# LightStateRF.net
KiCad netlist of a schematic drawn in Altium Designer
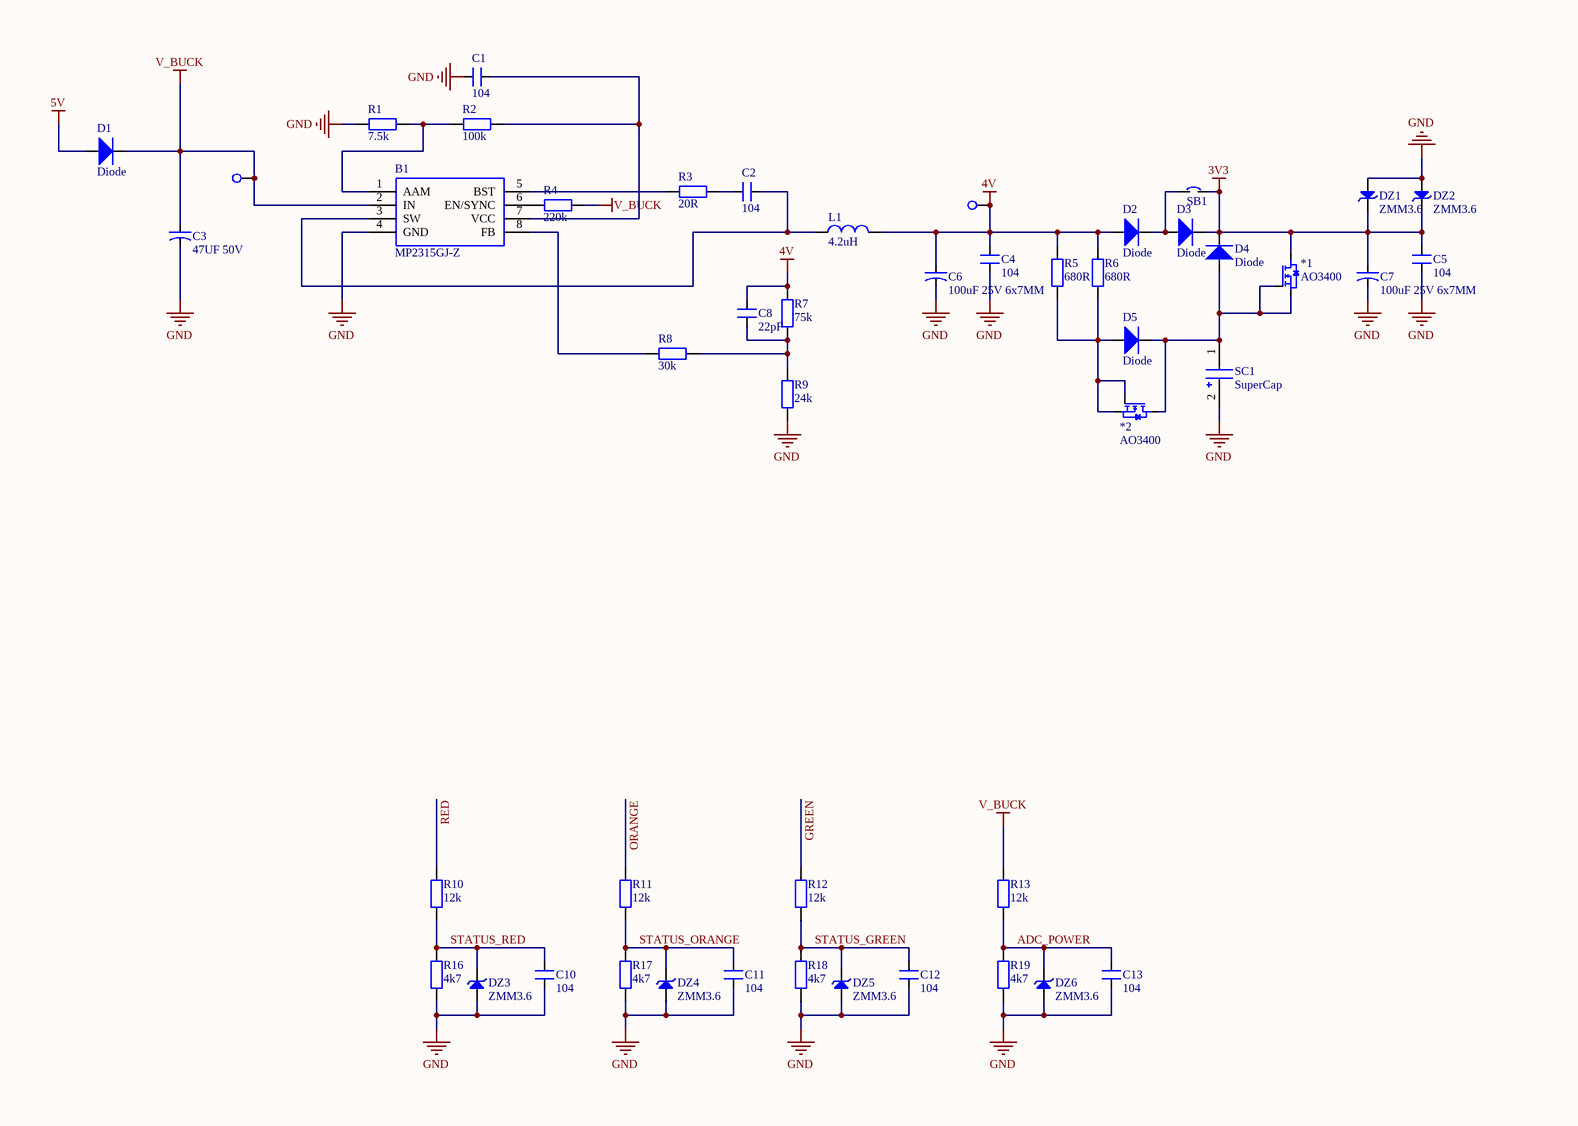
[diagram p0: LightStateRF.SchDoc, top left]
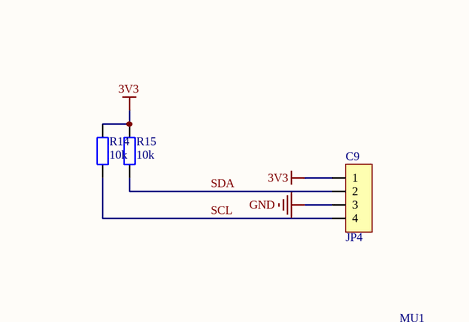
[diagram p1: LightStateRF.SchDoc, top right]
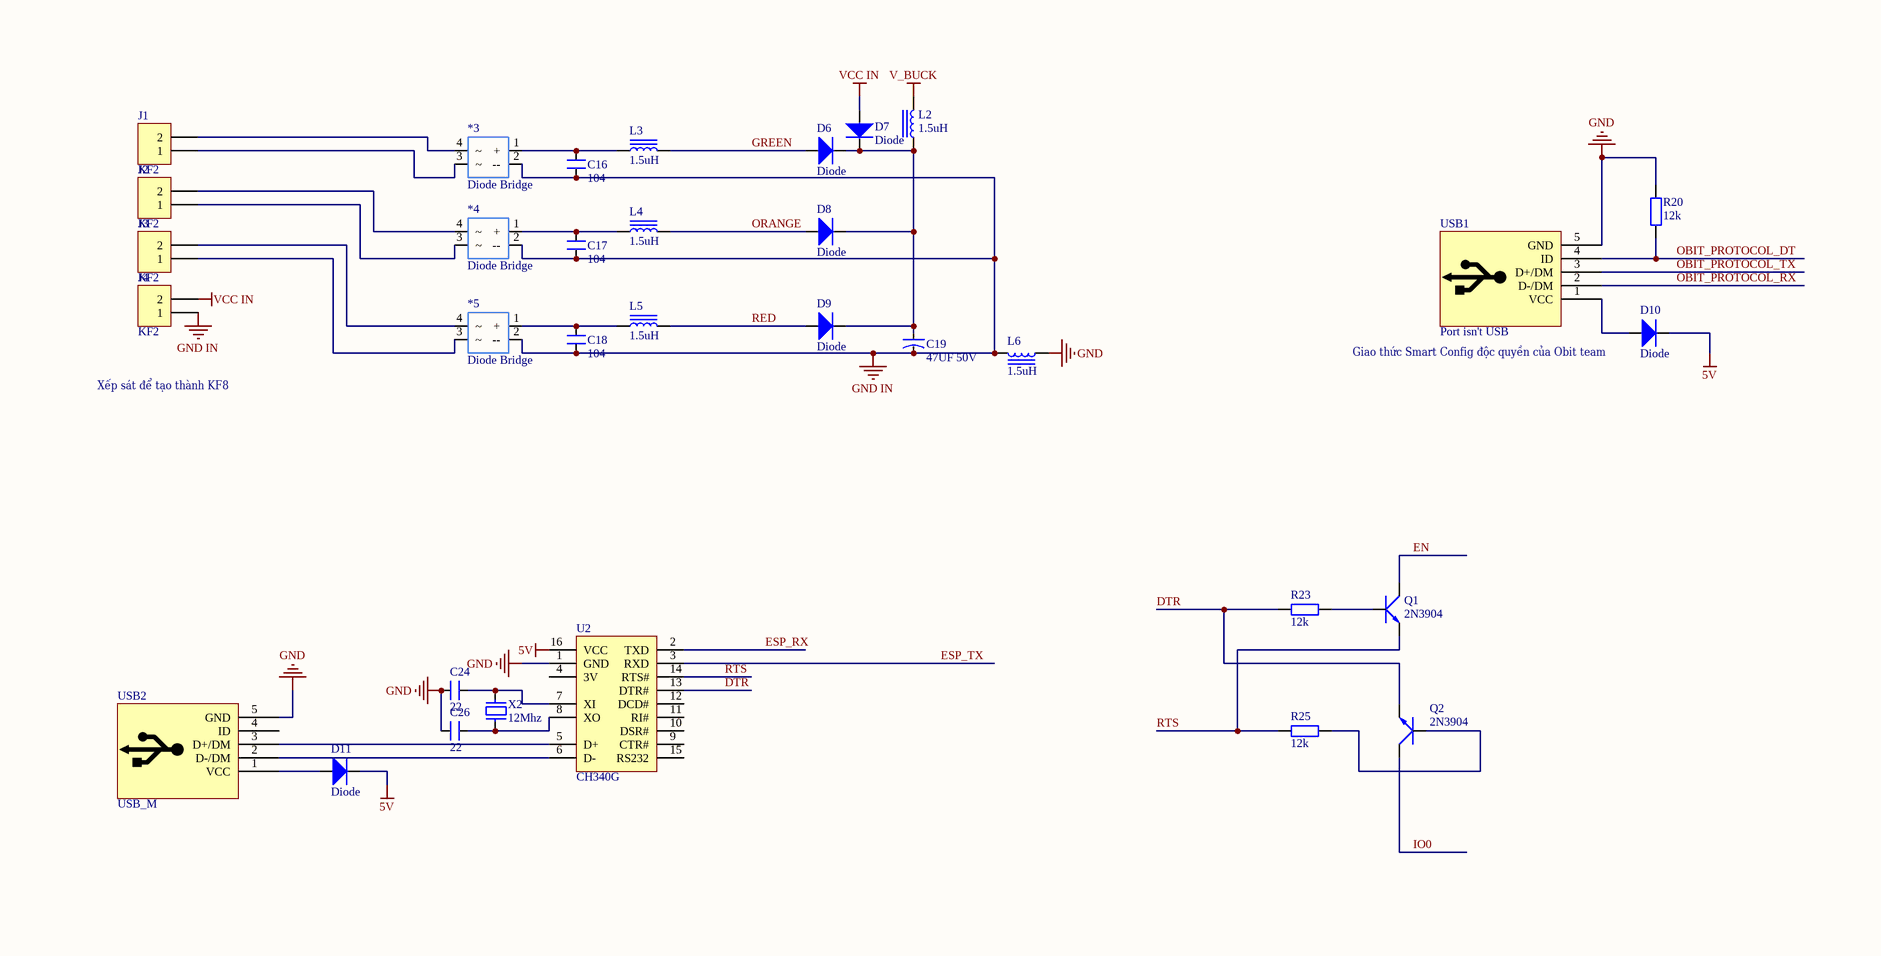
[diagram p2: LightStateRF.SchDoc, bottom left]
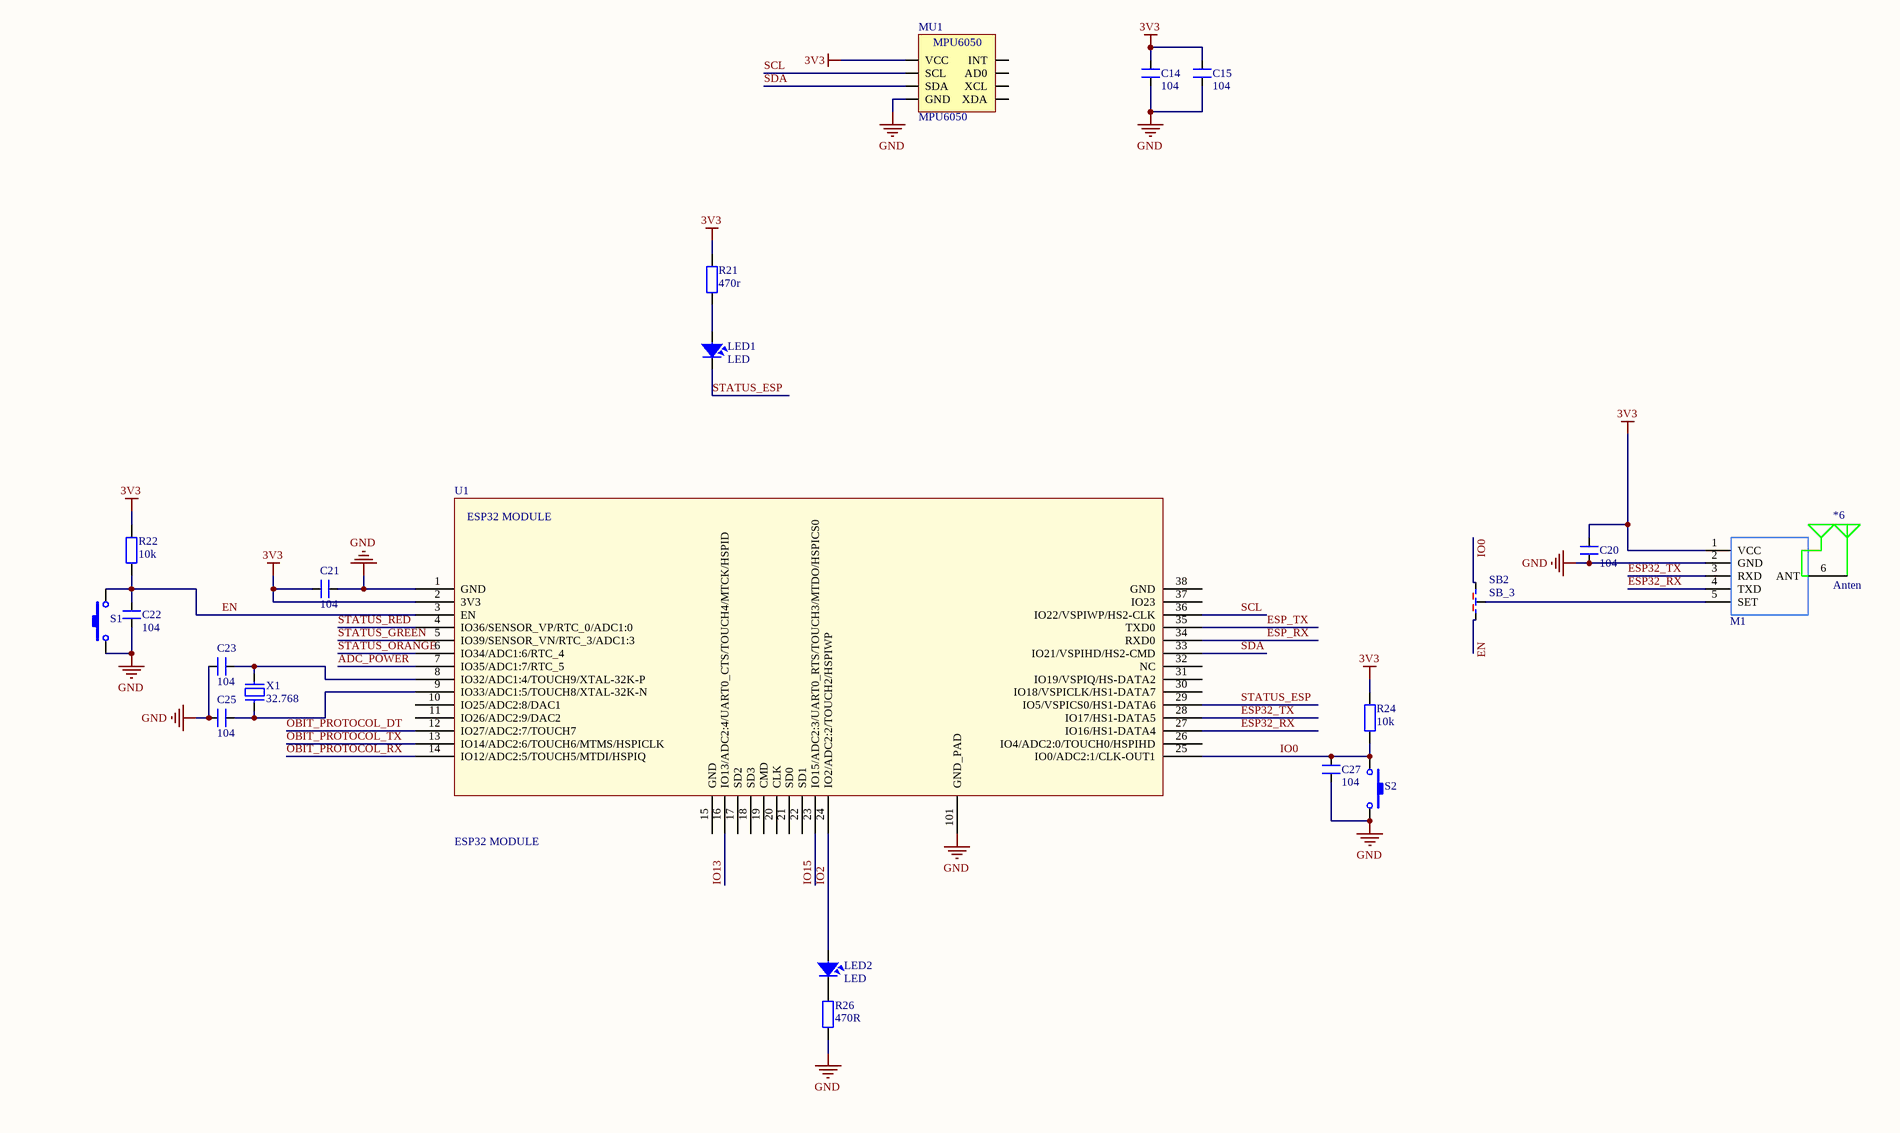
[diagram p3: LightStateRF.SchDoc, bottom right]

(export (version "E")
  (design (tool "Eeschema 10.0.6"))
  (components
    (comp (ref "*1") (value "AO3400") (footprint "SOT23-123") (libsource (lib "OBIT_TESLA") (part "AO3400")))
    (comp (ref "*2") (value "AO3400") (footprint "SOT23-123") (libsource (lib "OBIT_TESLA") (part "AO3400")))
    (comp (ref "*3")
      (value "Diode Bridge")
      (footprint "Diode Bridge 1A")
      (libsource (lib "OBIT_TESLA") (part "Diode Bridge"))
    )
    (comp (ref "*4")
      (value "Diode Bridge")
      (footprint "Diode Bridge 1A")
      (libsource (lib "OBIT_TESLA") (part "Diode Bridge"))
    )
    (comp (ref "*5")
      (value "Diode Bridge")
      (footprint "Diode Bridge 1A")
      (libsource (lib "OBIT_TESLA") (part "Diode Bridge"))
    )
    (comp (ref "*6")
      (value "Anten")
      (footprint "LOXO_433_NGANG")
      (libsource (lib "OBIT_TESLA") (part "Anten"))
    )
    (comp (ref "*TP1") (value "TP") (footprint "TP") (libsource (lib "OBIT_TESLA") (part "TP")))
    (comp (ref "*TP2") (value "TP") (footprint "TP") (libsource (lib "OBIT_TESLA") (part "TP")))
    (comp (ref "B1")
      (value "MP2315GJ-Z")
      (footprint "SOT65P280X100-8N")
      (description "Switching Voltage Regulators 3A 24V 500kHz Sync buck")
      (libsource (lib "OBIT_TESLA") (part "MP2315GJ-Z"))
    )
    (comp (ref "C1")
      (value "104")
      (footprint "SM-0805")
      (description "Cap SMD")
      (libsource (lib "OBIT_TESLA") (part "CM"))
    )
    (comp (ref "C2")
      (value "104")
      (footprint "SM-0805")
      (description "Cap SMD")
      (libsource (lib "OBIT_TESLA") (part "CM"))
    )
    (comp (ref "C3")
      (value "47UF 50V")
      (footprint "CAP-ALU-SMD-6.3x7.7x2.2")
      (description "Tụ Nhôm 47UF 50V 6.3x5.5MM")
      (fields (field (name "PUBLISHER") "Altium Limited"))
      (libsource (lib "Tesla_Thinh") (part "CN-ALU-SMD"))
    )
    (comp (ref "C4")
      (value "104")
      (footprint "SM-0805")
      (description "Cap SMD")
      (libsource (lib "OBIT_TESLA") (part "CM"))
    )
    (comp (ref "C5")
      (value "104")
      (footprint "SM-0805")
      (description "Cap SMD")
      (libsource (lib "OBIT_TESLA") (part "CM"))
    )
    (comp (ref "C6")
      (value "100uF 25V 6x7MM")
      (footprint "CAP-ALU-SMD-6.3x7.7x2.2")
      (description "Polarized Capacitor (Axial)")
      (fields (field (name "PUBLISHER") "Altium Limited"))
      (libsource (lib "Tesla_Thinh") (part "CN-ALU-SMD"))
    )
    (comp (ref "C7")
      (value "100uF 25V 6x7MM")
      (footprint "CAP-ALU-SMD-6.3x7.7x2.2")
      (description "Polarized Capacitor (Axial)")
      (fields (field (name "PUBLISHER") "Altium Limited"))
      (libsource (lib "Tesla_Thinh") (part "CN-ALU-SMD"))
    )
    (comp (ref "C8")
      (value "22pF")
      (footprint "SM-0805")
      (description "Cap SMD")
      (libsource (lib "OBIT_TESLA") (part "CM"))
    )
    (comp (ref "C9")
      (value "JP4")
      (footprint "JP4-C1T")
      (description "WR-PHD 2.54 mm Angled Socket Header")
      (fields
        (field (name "MANUFACTURER") "Würth Elektronik eiSos GmbH")
        (field (name "PARTNO") "613004143121")
        (field (name "CREATED BY") "Karrer Zheng")
      )
      (libsource (lib "OBIT_TESLA") (part "JP4"))
    )
    (comp (ref "C10")
      (value "104")
      (footprint "SM-0805")
      (description "Cap SMD")
      (libsource (lib "OBIT_TESLA") (part "CM"))
    )
    (comp (ref "C11")
      (value "104")
      (footprint "SM-0805")
      (description "Cap SMD")
      (libsource (lib "OBIT_TESLA") (part "CM"))
    )
    (comp (ref "C12")
      (value "104")
      (footprint "SM-0805")
      (description "Cap SMD")
      (libsource (lib "OBIT_TESLA") (part "CM"))
    )
    (comp (ref "C13")
      (value "104")
      (footprint "SM-0805")
      (description "Cap SMD")
      (libsource (lib "OBIT_TESLA") (part "CM"))
    )
    (comp (ref "C14")
      (value "104")
      (footprint "SM-0805")
      (description "Cap SMD")
      (libsource (lib "OBIT_TESLA") (part "CM"))
    )
    (comp (ref "C15")
      (value "104")
      (footprint "SM-0805")
      (description "Cap SMD")
      (libsource (lib "OBIT_TESLA") (part "CM"))
    )
    (comp (ref "C16")
      (value "104")
      (footprint "SM-0805")
      (description "Cap SMD")
      (libsource (lib "OBIT_TESLA") (part "CM"))
    )
    (comp (ref "C17")
      (value "104")
      (footprint "SM-0805")
      (description "Cap SMD")
      (libsource (lib "OBIT_TESLA") (part "CM"))
    )
    (comp (ref "C18")
      (value "104")
      (footprint "SM-0805")
      (description "Cap SMD")
      (libsource (lib "OBIT_TESLA") (part "CM"))
    )
    (comp (ref "C19")
      (value "47UF 50V")
      (footprint "CAP-ALU-SMD-6.3x7.7x2.2")
      (description "Tụ Nhôm 47UF 50V 6.3x5.5MM")
      (fields (field (name "PUBLISHER") "Altium Limited"))
      (libsource (lib "Tesla_Thinh") (part "CN-ALU-SMD"))
    )
    (comp (ref "C20")
      (value "104")
      (footprint "SM-0805")
      (description "Cap SMD")
      (libsource (lib "OBIT_TESLA") (part "CM"))
    )
    (comp (ref "C21")
      (value "104")
      (footprint "SM-0805")
      (description "Cap SMD")
      (libsource (lib "OBIT_TESLA") (part "CM"))
    )
    (comp (ref "C22")
      (value "104")
      (footprint "SM-0805")
      (description "Cap SMD")
      (libsource (lib "OBIT_TESLA") (part "CM"))
    )
    (comp (ref "C23")
      (value "104")
      (footprint "SM-0805")
      (description "Cap SMD")
      (libsource (lib "OBIT_TESLA") (part "CM"))
    )
    (comp (ref "C24")
      (value "22")
      (footprint "SM-0805")
      (description "Cap SMD")
      (libsource (lib "OBIT_TESLA") (part "CM"))
    )
    (comp (ref "C25")
      (value "104")
      (footprint "SM-0805")
      (description "Cap SMD")
      (libsource (lib "OBIT_TESLA") (part "CM"))
    )
    (comp (ref "C26")
      (value "22")
      (footprint "SM-0805")
      (description "Cap SMD")
      (libsource (lib "OBIT_TESLA") (part "CM"))
    )
    (comp (ref "C27")
      (value "104")
      (footprint "SM-0805")
      (description "Cap SMD")
      (libsource (lib "OBIT_TESLA") (part "CM"))
    )
    (comp (ref "D1") (value "Diode") (footprint "SOD123") (libsource (lib "OBIT_TESLA") (part "Diode")))
    (comp (ref "D2") (value "Diode") (footprint "DIO-SMD-123") (libsource (lib "OBIT_TESLA") (part "Diode")))
    (comp (ref "D3") (value "Diode") (footprint "DIO-SMD-123") (libsource (lib "OBIT_TESLA") (part "Diode")))
    (comp (ref "D4") (value "Diode") (footprint "DIO-SMD-123") (libsource (lib "OBIT_TESLA") (part "Diode")))
    (comp (ref "D5") (value "Diode") (footprint "SOD123") (libsource (lib "OBIT_TESLA") (part "Diode")))
    (comp (ref "D6") (value "Diode") (footprint "DIO-SMD-106") (libsource (lib "OBIT_TESLA") (part "Diode")))
    (comp (ref "D7") (value "Diode") (footprint "DIO-SMD-106") (libsource (lib "OBIT_TESLA") (part "Diode")))
    (comp (ref "D8") (value "Diode") (footprint "DIO-SMD-106") (libsource (lib "OBIT_TESLA") (part "Diode")))
    (comp (ref "D9") (value "Diode") (footprint "DIO-SMD-106") (libsource (lib "OBIT_TESLA") (part "Diode")))
    (comp (ref "D10") (value "Diode") (footprint "DIO-SMD-106") (libsource (lib "OBIT_TESLA") (part "Diode")))
    (comp (ref "D11") (value "Diode") (footprint "DIO-SMD-106") (libsource (lib "OBIT_TESLA") (part "Diode")))
    (comp (ref "DZ1")
      (value "ZMM3.6")
      (footprint "SOD123")
      (description "DIODE GEN PURP 75V 200MA LLDS")
      (libsource (lib "Library") (part "DIODE Zener"))
    )
    (comp (ref "DZ2")
      (value "ZMM3.6")
      (footprint "DIO-SMD-123")
      (description "DIODE GEN PURP 75V 200MA LLDS")
      (libsource (lib "Library") (part "DIODE Zener"))
    )
    (comp (ref "DZ3")
      (value "ZMM3.6")
      (footprint "SOD123")
      (description "DIODE GEN PURP 75V 200MA LLDS")
      (libsource (lib "Library") (part "DIODE Zener"))
    )
    (comp (ref "DZ4")
      (value "ZMM3.6")
      (footprint "SOD123")
      (description "DIODE GEN PURP 75V 200MA LLDS")
      (libsource (lib "Library") (part "DIODE Zener"))
    )
    (comp (ref "DZ5")
      (value "ZMM3.6")
      (footprint "SOD123")
      (description "DIODE GEN PURP 75V 200MA LLDS")
      (libsource (lib "Library") (part "DIODE Zener"))
    )
    (comp (ref "DZ6")
      (value "ZMM3.6")
      (footprint "SOD123")
      (description "DIODE GEN PURP 75V 200MA LLDS")
      (libsource (lib "Library") (part "DIODE Zener"))
    )
    (comp (ref "J1")
      (value "KF2")
      (footprint "KF2-5.08")
      (fields
        (field (name "MANUFACTURER") "Würth Elektronik eiSos GmbH")
        (field (name "PARTNO") "691103110002")
        (field (name "CREATED BY") "Karrer Zheng")
      )
      (libsource (lib "Tesla_Thinh") (part "KF2"))
    )
    (comp (ref "J2")
      (value "KF2")
      (footprint "KF2-5.08")
      (fields
        (field (name "MANUFACTURER") "Würth Elektronik eiSos GmbH")
        (field (name "PARTNO") "691103110002")
        (field (name "CREATED BY") "Karrer Zheng")
      )
      (libsource (lib "Tesla_Thinh") (part "KF2"))
    )
    (comp (ref "J3")
      (value "KF2")
      (footprint "KF2-5.08")
      (fields
        (field (name "MANUFACTURER") "Würth Elektronik eiSos GmbH")
        (field (name "PARTNO") "691103110002")
        (field (name "CREATED BY") "Karrer Zheng")
      )
      (libsource (lib "Tesla_Thinh") (part "KF2"))
    )
    (comp (ref "J4")
      (value "KF2")
      (footprint "KF2-5.08")
      (fields
        (field (name "MANUFACTURER") "Würth Elektronik eiSos GmbH")
        (field (name "PARTNO") "691103110002")
        (field (name "CREATED BY") "Karrer Zheng")
      )
      (libsource (lib "Tesla_Thinh") (part "KF2"))
    )
    (comp (ref "L1")
      (value "4.2uH")
      (footprint "IND 4532-2P")
      (libsource (lib "AltiumLibraryTieuBao (1)") (part "INDUCTOR B"))
    )
    (comp (ref "L2")
      (value "1.5uH")
      (footprint "FER 0805/2012")
      (description "SMT Inductor")
      (libsource (lib "OBIT_TESLA") (part "Inductor"))
    )
    (comp (ref "L3")
      (value "1.5uH")
      (footprint "FER 0805/2012")
      (description "SMT Inductor")
      (libsource (lib "OBIT_TESLA") (part "Inductor"))
    )
    (comp (ref "L4")
      (value "1.5uH")
      (footprint "FER 0805/2012")
      (description "SMT Inductor")
      (libsource (lib "OBIT_TESLA") (part "Inductor"))
    )
    (comp (ref "L5")
      (value "1.5uH")
      (footprint "FER 0805/2012")
      (description "SMT Inductor")
      (libsource (lib "OBIT_TESLA") (part "Inductor"))
    )
    (comp (ref "L6")
      (value "1.5uH")
      (footprint "FER 0805/2012")
      (description "SMT Inductor")
      (libsource (lib "OBIT_TESLA") (part "Inductor"))
    )
    (comp (ref "LED1")
      (value "LED")
      (footprint "SM-LED-0805-Blue")
      (libsource (lib "OBIT_TESLA") (part "LED"))
    )
    (comp (ref "LED2")
      (value "LED")
      (footprint "SM-LED-0805-Blue")
      (libsource (lib "OBIT_TESLA") (part "LED"))
    )
    (comp (ref "M1")
      (value "CC1101")
      (footprint "CC1101 UART HC11")
      (description "OBIT TEAM\r\nCC1101 UART 433MHZ")
      (libsource (lib "OBIT_TESLA") (part "CC1101 UART HC11"))
    )
    (comp (ref "MU1")
      (value "MPU6050")
      (footprint "MPU6050")
      (fields
        (field (name "MANUFACTURER") "Würth Elektronik eiSos GmbH")
        (field (name "PARTNO") "613004143121")
        (field (name "CREATED BY") "Karrer Zheng")
      )
      (libsource (lib "Tesla_Thinh") (part "MPU6050"))
    )
    (comp (ref "Q1")
      (value "2N3904")
      (footprint "SOT23-231")
      (description "NPN 600mW, ECB")
      (libsource (lib "OBIT_TESLA") (part "2N3904"))
    )
    (comp (ref "Q2")
      (value "2N3904")
      (footprint "SOT23-231")
      (description "NPN 600mW, ECB")
      (libsource (lib "OBIT_TESLA") (part "2N3904"))
    )
    (comp (ref "R1")
      (value "7.5k")
      (footprint "RES-SMD-0805")
      (description "Resistor R1/4W")
      (libsource (lib "OBIT_TESLA") (part "R"))
    )
    (comp (ref "R2")
      (value "100k")
      (footprint "RES-SMD-0805")
      (description "Resistor R1/4W")
      (libsource (lib "OBIT_TESLA") (part "R"))
    )
    (comp (ref "R3")
      (value "20R")
      (footprint "RES-SMD-0805")
      (description "Resistor R1/4W")
      (libsource (lib "OBIT_TESLA") (part "R"))
    )
    (comp (ref "R4")
      (value "220k")
      (footprint "RES-SMD-0805")
      (description "Resistor R1/4W")
      (libsource (lib "OBIT_TESLA") (part "R"))
    )
    (comp (ref "R5")
      (value "680R")
      (footprint "RES-SMD-0805")
      (description "Resistor R1/4W")
      (libsource (lib "OBIT_TESLA") (part "R"))
    )
    (comp (ref "R6")
      (value "680R")
      (footprint "RES-SMD-0805")
      (description "Resistor R1/4W")
      (libsource (lib "OBIT_TESLA") (part "R"))
    )
    (comp (ref "R7")
      (value "75k")
      (footprint "RES-SMD-0805")
      (description "Resistor R1/4W")
      (libsource (lib "OBIT_TESLA") (part "R"))
    )
    (comp (ref "R8")
      (value "30k")
      (footprint "RES-SMD-0805")
      (description "Resistor R1/4W")
      (libsource (lib "OBIT_TESLA") (part "R"))
    )
    (comp (ref "R9")
      (value "24k")
      (footprint "RES-SMD-0805")
      (description "Resistor R1/4W")
      (libsource (lib "OBIT_TESLA") (part "R"))
    )
    (comp (ref "R10")
      (value "12k")
      (footprint "RES-SMD-0805")
      (description "Resistor R1/4W")
      (libsource (lib "OBIT_TESLA") (part "R"))
    )
    (comp (ref "R11")
      (value "12k")
      (footprint "RES-SMD-0805")
      (description "Resistor R1/4W")
      (libsource (lib "OBIT_TESLA") (part "R"))
    )
    (comp (ref "R12")
      (value "12k")
      (footprint "RES-SMD-0805")
      (description "Resistor R1/4W")
      (libsource (lib "OBIT_TESLA") (part "R"))
    )
    (comp (ref "R13")
      (value "12k")
      (footprint "RES-SMD-0805")
      (description "Resistor R1/4W")
      (libsource (lib "OBIT_TESLA") (part "R"))
    )
    (comp (ref "R14")
      (value "10k")
      (footprint "RES-SMD-0805")
      (description "Resistor R1/4W")
      (libsource (lib "OBIT_TESLA") (part "R"))
    )
    (comp (ref "R15")
      (value "10k")
      (footprint "RES-SMD-0805")
      (description "Resistor R1/4W")
      (libsource (lib "OBIT_TESLA") (part "R"))
    )
    (comp (ref "R16")
      (value "4k7")
      (footprint "RES-SMD-0805")
      (description "Resistor R1/4W")
      (libsource (lib "OBIT_TESLA") (part "R"))
    )
    (comp (ref "R17")
      (value "4k7")
      (footprint "RES-SMD-0805")
      (description "Resistor R1/4W")
      (libsource (lib "OBIT_TESLA") (part "R"))
    )
    (comp (ref "R18")
      (value "4k7")
      (footprint "RES-SMD-0805")
      (description "Resistor R1/4W")
      (libsource (lib "OBIT_TESLA") (part "R"))
    )
    (comp (ref "R19")
      (value "4k7")
      (footprint "RES-SMD-0805")
      (description "Resistor R1/4W")
      (libsource (lib "OBIT_TESLA") (part "R"))
    )
    (comp (ref "R20")
      (value "12k")
      (footprint "RES-SMD-0805")
      (description "Resistor R1/4W")
      (libsource (lib "OBIT_TESLA") (part "R"))
    )
    (comp (ref "R21")
      (value "470r")
      (footprint "RES-SMD-0805")
      (description "Resistor R1/4W")
      (libsource (lib "OBIT_TESLA") (part "R"))
    )
    (comp (ref "R22")
      (value "10k")
      (footprint "RES-SMD-0805")
      (description "Resistor R1/4W")
      (libsource (lib "OBIT_TESLA") (part "R"))
    )
    (comp (ref "R23")
      (value "12k")
      (footprint "RES-SMD-0805")
      (description "Resistor R1/4W")
      (libsource (lib "OBIT_TESLA") (part "R"))
    )
    (comp (ref "R24")
      (value "10k")
      (footprint "RES-SMD-0805")
      (description "Resistor R1/4W")
      (libsource (lib "OBIT_TESLA") (part "R"))
    )
    (comp (ref "R25")
      (value "12k")
      (footprint "RES-SMD-0805")
      (description "Resistor R1/4W")
      (libsource (lib "OBIT_TESLA") (part "R"))
    )
    (comp (ref "R26")
      (value "470R")
      (footprint "RES-SMD-0805")
      (description "Resistor R1/4W")
      (libsource (lib "OBIT_TESLA") (part "R"))
    )
    (comp (ref "S1")
      (value "SW")
      (footprint "BUTTON-SMD 2PIN")
      (description "Switch-Button")
      (fields (field (name "PUBLISHER") "Altium Limited"))
      (libsource (lib "OBIT_TESLA") (part "SW-Button"))
    )
    (comp (ref "S2")
      (value "SW")
      (footprint "BUTTON-SMD 2PIN")
      (description "Switch-Button")
      (fields (field (name "PUBLISHER") "Altium Limited"))
      (libsource (lib "OBIT_TESLA") (part "SW-Button"))
    )
    (comp (ref "SB1") (value "SB") (footprint "SB") (libsource (lib "OBIT_TESLA") (part "SB")))
    (comp (ref "SB2") (value "SB_3") (footprint "SB_3") (libsource (lib "OBIT_TESLA") (part "SB_3")))
    (comp (ref "SC1")
      (value "SuperCap")
      (footprint "SuperCapacitor")
      (libsource (lib "OBIT_TESLA") (part "5.5V 0.22F"))
    )
    (comp (ref "U1")
      (value "ESP32 MODULE")
      (footprint "ESP32S")
      (libsource (lib "OBIT_TESLA") (part "ESP32 MODULE"))
    )
    (comp (ref "U2")
      (value "CH340G")
      (footprint "SO16")
      (description "High and Low Side Driver")
      (fields (field (name "PUBLISHER") "Altium Limited"))
      (libsource (lib "OBIT_TESLA") (part "CH340G"))
    )
    (comp (ref "USB1")
      (value "Port isn't USB")
      (footprint "USB-M1")
      (libsource (lib "OBIT_TESLA") (part "USB_M"))
    )
    (comp (ref "USB2") (value "USB_M") (footprint "USB-M1") (libsource (lib "OBIT_TESLA") (part "USB_M")))
    (comp (ref "X1")
      (value "32.768")
      (footprint "XT32k")
      (description "Crystal, 32.768 KHz, -40 to 85 degC, 3.2 x 1.5 x 0.9 mm SMD")
      (libsource (lib "OBIT_TESLA") (part "XT2"))
    )
    (comp (ref "X2")
      (value "12Mhz")
      (footprint "XT2")
      (description "Crystal, 32.768 KHz, -40 to 85 degC, 3.2 x 1.5 x 0.9 mm SMD")
      (libsource (lib "OBIT_TESLA") (part "XT2"))
    )
  )
  (nets
    (net (code "1") (name "/ADC_POWER") (class "Default")
      (node (ref "C13") (pin "2") (pinfunction "2_2") (pintype "passive"))
      (node (ref "DZ6") (pin "2") (pinfunction "K_2") (pintype "passive"))
      (node (ref "R13") (pin "2") (pinfunction "2_2") (pintype "passive"))
      (node (ref "R19") (pin "1") (pinfunction "1_1") (pintype "passive"))
      (node (ref "U1") (pin "7") (pinfunction "IO35/ADC1:7/RTC_5_7") (pintype "passive"))
    )
    (net (code "2") (name "/DTR") (class "Default")
      (node (ref "Q2") (pin "1") (pinfunction "E_1") (pintype "passive"))
      (node (ref "R23") (pin "2") (pinfunction "2_2") (pintype "passive"))
      (node (ref "U2") (pin "13") (pinfunction "DTR#_13") (pintype "passive"))
    )
    (net (code "3") (name "/EN") (class "Default")
      (node (ref "C22") (pin "1") (pinfunction "1_1") (pintype "passive"))
      (node (ref "Q1") (pin "3") (pinfunction "C_3") (pintype "passive"))
      (node (ref "R22") (pin "1") (pinfunction "1_1") (pintype "passive"))
      (node (ref "S1") (pin "2") (pinfunction "2_2") (pintype "passive"))
      (node (ref "SB2") (pin "1") (pinfunction "1_1") (pintype "passive"))
      (node (ref "U1") (pin "3") (pinfunction "EN_3") (pintype "power_in"))
    )
    (net (code "4") (name "/ESP32_RX") (class "Default")
      (node (ref "M1") (pin "4") (pinfunction "TXD_4") (pintype "passive"))
      (node (ref "U1") (pin "27") (pinfunction "IO16/HS1-DATA4_27") (pintype "passive"))
    )
    (net (code "5") (name "/ESP32_TX") (class "Default")
      (node (ref "M1") (pin "3") (pinfunction "RXD_3") (pintype "passive"))
      (node (ref "U1") (pin "28") (pinfunction "IO17/HS1-DATA5_28") (pintype "passive"))
    )
    (net (code "6") (name "/ESP_RX") (class "Default")
      (node (ref "U1") (pin "34") (pinfunction "RXD0_34") (pintype "passive"))
      (node (ref "U2") (pin "2") (pinfunction "TXD_2") (pintype "passive"))
    )
    (net (code "7") (name "/ESP_TX") (class "Default")
      (node (ref "U1") (pin "35") (pinfunction "TXD0_35") (pintype "passive"))
      (node (ref "U2") (pin "3") (pinfunction "RXD_3") (pintype "passive"))
    )
    (net (code "8") (name "/GREEN") (class "Default")
      (node (ref "D6") (pin "1") (pinfunction "1_1") (pintype "passive"))
      (node (ref "L3") (pin "2") (pinfunction "2_2") (pintype "passive"))
      (node (ref "R12") (pin "1") (pinfunction "1_1") (pintype "passive"))
    )
    (net (code "9") (name "/IO0") (class "Default")
      (node (ref "C27") (pin "2") (pinfunction "2_2") (pintype "passive"))
      (node (ref "Q2") (pin "3") (pinfunction "C_3") (pintype "passive"))
      (node (ref "R24") (pin "2") (pinfunction "2_2") (pintype "passive"))
      (node (ref "S2") (pin "1") (pinfunction "1_1") (pintype "passive"))
      (node (ref "SB2") (pin "3") (pinfunction "3_3") (pintype "passive"))
      (node (ref "U1") (pin "25") (pinfunction "IO0/ADC2:1/CLK-OUT1_25") (pintype "passive"))
    )
    (net (code "10") (name "/IO2") (class "Default")
      (node (ref "LED2") (pin "1") (pinfunction "1_1") (pintype "passive"))
      (node (ref "U1") (pin "24") (pinfunction "IO2/ADC2:2/TOUCH2/HSPIWP_24") (pintype "passive"))
    )
    (net (code "11") (name "/IO13") (class "Default")
      (node (ref "U1") (pin "16") (pinfunction "IO13/ADC2:4/UART0_CTS/TOUCH4/MTCK/HSPID_16") (pintype "passive"))
    )
    (net (code "12") (name "/IO15") (class "Default")
      (node (ref "U1") (pin "23") (pinfunction "IO15/ADC2:3/UART0_RTS/TOUCH3/MTDO/HSPICS0_23") (pintype "passive"))
    )
    (net (code "13") (name "/OBIT_PROTOCOL_DT") (class "Default")
      (node (ref "R20") (pin "2") (pinfunction "2_2") (pintype "passive"))
      (node (ref "U1") (pin "12") (pinfunction "IO27/ADC2:7/TOUCH7_12") (pintype "passive"))
      (node (ref "USB1") (pin "4") (pinfunction "ID_4") (pintype "passive"))
    )
    (net (code "14") (name "/OBIT_PROTOCOL_RX") (class "Default")
      (node (ref "U1") (pin "14") (pinfunction "IO12/ADC2:5/TOUCH5/MTDI/HSPIQ_14") (pintype "passive"))
      (node (ref "USB1") (pin "2") (pinfunction "D-/DM_2") (pintype "passive"))
    )
    (net (code "15") (name "/OBIT_PROTOCOL_TX") (class "Default")
      (node (ref "U1") (pin "13") (pinfunction "IO14/ADC2:6/TOUCH6/MTMS/HSPICLK_13") (pintype "passive"))
      (node (ref "USB1") (pin "3") (pinfunction "D+/DM_3") (pintype "passive"))
    )
    (net (code "16") (name "/ORANGE") (class "Default")
      (node (ref "D8") (pin "1") (pinfunction "1_1") (pintype "passive"))
      (node (ref "L4") (pin "2") (pinfunction "2_2") (pintype "passive"))
      (node (ref "R11") (pin "1") (pinfunction "1_1") (pintype "passive"))
    )
    (net (code "17") (name "/RED") (class "Default")
      (node (ref "D9") (pin "1") (pinfunction "1_1") (pintype "passive"))
      (node (ref "L5") (pin "2") (pinfunction "2_2") (pintype "passive"))
      (node (ref "R10") (pin "1") (pinfunction "1_1") (pintype "passive"))
    )
    (net (code "18") (name "/RTS") (class "Default")
      (node (ref "Q1") (pin "1") (pinfunction "E_1") (pintype "passive"))
      (node (ref "R25") (pin "2") (pinfunction "2_2") (pintype "passive"))
      (node (ref "U2") (pin "14") (pinfunction "RTS#_14") (pintype "passive"))
    )
    (net (code "19") (name "/SCL") (class "Default")
      (node (ref "C9") (pin "4") (pinfunction "4_4") (pintype "passive"))
      (node (ref "MU1") (pin "3") (pinfunction "SCL_3") (pintype "passive"))
      (node (ref "R14") (pin "1") (pinfunction "1_1") (pintype "passive"))
      (node (ref "U1") (pin "36") (pinfunction "IO22/VSPIWP/HS2-CLK_36") (pintype "passive"))
    )
    (net (code "20") (name "/SDA") (class "Default")
      (node (ref "C9") (pin "2") (pinfunction "2_2") (pintype "passive"))
      (node (ref "MU1") (pin "4") (pinfunction "SDA_4") (pintype "passive"))
      (node (ref "R15") (pin "1") (pinfunction "1_1") (pintype "passive"))
      (node (ref "U1") (pin "33") (pinfunction "IO21/VSPIHD/HS2-CMD_33") (pintype "passive"))
    )
    (net (code "21") (name "/STATUS_ESP") (class "Default")
      (node (ref "LED1") (pin "2") (pinfunction "2_2") (pintype "passive"))
      (node (ref "U1") (pin "29") (pinfunction "IO5/VSPICS0/HS1-DATA6_29") (pintype "passive"))
    )
    (net (code "22") (name "/STATUS_GREEN") (class "Default")
      (node (ref "C12") (pin "2") (pinfunction "2_2") (pintype "passive"))
      (node (ref "DZ5") (pin "2") (pinfunction "K_2") (pintype "passive"))
      (node (ref "R12") (pin "2") (pinfunction "2_2") (pintype "passive"))
      (node (ref "R18") (pin "1") (pinfunction "1_1") (pintype "passive"))
      (node (ref "U1") (pin "5") (pinfunction "IO39/SENSOR_VN/RTC_3/ADC1:3_5") (pintype "passive"))
    )
    (net (code "23") (name "/STATUS_ORANGE") (class "Default")
      (node (ref "C11") (pin "2") (pinfunction "2_2") (pintype "passive"))
      (node (ref "DZ4") (pin "2") (pinfunction "K_2") (pintype "passive"))
      (node (ref "R11") (pin "2") (pinfunction "2_2") (pintype "passive"))
      (node (ref "R17") (pin "1") (pinfunction "1_1") (pintype "passive"))
      (node (ref "U1") (pin "6") (pinfunction "IO34/ADC1:6/RTC_4_6") (pintype "passive"))
    )
    (net (code "24") (name "/STATUS_RED") (class "Default")
      (node (ref "C10") (pin "2") (pinfunction "2_2") (pintype "passive"))
      (node (ref "DZ3") (pin "2") (pinfunction "K_2") (pintype "passive"))
      (node (ref "R10") (pin "2") (pinfunction "2_2") (pintype "passive"))
      (node (ref "R16") (pin "1") (pinfunction "1_1") (pintype "passive"))
      (node (ref "U1") (pin "4") (pinfunction "IO36/SENSOR_VP/RTC_0/ADC1:0_4") (pintype "passive"))
    )
    (net (code "25") (name "3V3") (class "Default")
      (node (ref "*1") (pin "2") (pintype "passive"))
      (node (ref "C14") (pin "2") (pinfunction "2_2") (pintype "passive"))
      (node (ref "C15") (pin "2") (pinfunction "2_2") (pintype "passive"))
      (node (ref "C20") (pin "2") (pinfunction "2_2") (pintype "passive"))
      (node (ref "C21") (pin "2") (pinfunction "2_2") (pintype "passive"))
      (node (ref "C5") (pin "2") (pinfunction "2_2") (pintype "passive"))
      (node (ref "C7") (pin "1") (pinfunction "1_1") (pintype "passive"))
      (node (ref "C9") (pin "1") (pinfunction "1_1") (pintype "passive"))
      (node (ref "D3") (pin "2") (pinfunction "2_2") (pintype "passive"))
      (node (ref "D4") (pin "2") (pinfunction "2_2") (pintype "passive"))
      (node (ref "DZ1") (pin "2") (pinfunction "K_2") (pintype "passive"))
      (node (ref "DZ2") (pin "2") (pinfunction "K_2") (pintype "passive"))
      (node (ref "M1") (pin "1") (pinfunction "VCC_1") (pintype "passive"))
      (node (ref "MU1") (pin "1") (pinfunction "VCC_1") (pintype "passive"))
      (node (ref "R14") (pin "2") (pinfunction "2_2") (pintype "passive"))
      (node (ref "R15") (pin "2") (pinfunction "2_2") (pintype "passive"))
      (node (ref "R21") (pin "2") (pinfunction "2_2") (pintype "passive"))
      (node (ref "R22") (pin "2") (pinfunction "2_2") (pintype "passive"))
      (node (ref "R24") (pin "1") (pinfunction "1_1") (pintype "passive"))
      (node (ref "SB1") (pin "2") (pintype "passive"))
      (node (ref "U1") (pin "2") (pinfunction "3V3_2") (pintype "power_in"))
    )
    (net (code "26") (name "4V") (class "Default")
      (node (ref "*TP2") (pin "1") (pintype "passive"))
      (node (ref "C4") (pin "2") (pinfunction "2_2") (pintype "passive"))
      (node (ref "C6") (pin "1") (pinfunction "1_1") (pintype "passive"))
      (node (ref "C8") (pin "2") (pinfunction "2_2") (pintype "passive"))
      (node (ref "D2") (pin "1") (pinfunction "1_1") (pintype "passive"))
      (node (ref "L1") (pin "2") (pinfunction "2_2") (pintype "passive"))
      (node (ref "R5") (pin "1") (pinfunction "1_1") (pintype "passive"))
      (node (ref "R6") (pin "1") (pinfunction "1_1") (pintype "passive"))
      (node (ref "R7") (pin "1") (pinfunction "1_1") (pintype "passive"))
    )
    (net (code "27") (name "5V") (class "Default")
      (node (ref "D1") (pin "1") (pinfunction "1_1") (pintype "passive"))
      (node (ref "D10") (pin "2") (pinfunction "2_2") (pintype "passive"))
      (node (ref "D11") (pin "2") (pinfunction "2_2") (pintype "passive"))
      (node (ref "U2") (pin "16") (pinfunction "VCC_16") (pintype "passive"))
    )
    (net (code "28") (name "GND") (class "Default")
      (node (ref "B1") (pin "4") (pinfunction "GND_4") (pintype "passive"))
      (node (ref "C1") (pin "2") (pinfunction "2_2") (pintype "passive"))
      (node (ref "C10") (pin "1") (pinfunction "1_1") (pintype "passive"))
      (node (ref "C11") (pin "1") (pinfunction "1_1") (pintype "passive"))
      (node (ref "C12") (pin "1") (pinfunction "1_1") (pintype "passive"))
      (node (ref "C13") (pin "1") (pinfunction "1_1") (pintype "passive"))
      (node (ref "C14") (pin "1") (pinfunction "1_1") (pintype "passive"))
      (node (ref "C15") (pin "1") (pinfunction "1_1") (pintype "passive"))
      (node (ref "C20") (pin "1") (pinfunction "1_1") (pintype "passive"))
      (node (ref "C21") (pin "1") (pinfunction "1_1") (pintype "passive"))
      (node (ref "C22") (pin "2") (pinfunction "2_2") (pintype "passive"))
      (node (ref "C23") (pin "2") (pinfunction "2_2") (pintype "passive"))
      (node (ref "C24") (pin "2") (pinfunction "2_2") (pintype "passive"))
      (node (ref "C25") (pin "2") (pinfunction "2_2") (pintype "passive"))
      (node (ref "C26") (pin "2") (pinfunction "2_2") (pintype "passive"))
      (node (ref "C27") (pin "1") (pinfunction "1_1") (pintype "passive"))
      (node (ref "C3") (pin "2") (pinfunction "2_2") (pintype "passive"))
      (node (ref "C4") (pin "1") (pinfunction "1_1") (pintype "passive"))
      (node (ref "C5") (pin "1") (pinfunction "1_1") (pintype "passive"))
      (node (ref "C6") (pin "2") (pinfunction "2_2") (pintype "passive"))
      (node (ref "C7") (pin "2") (pinfunction "2_2") (pintype "passive"))
      (node (ref "C9") (pin "3") (pinfunction "3_3") (pintype "passive"))
      (node (ref "DZ1") (pin "1") (pinfunction "A_1") (pintype "passive"))
      (node (ref "DZ2") (pin "1") (pinfunction "A_1") (pintype "passive"))
      (node (ref "DZ3") (pin "1") (pinfunction "A_1") (pintype "passive"))
      (node (ref "DZ4") (pin "1") (pinfunction "A_1") (pintype "passive"))
      (node (ref "DZ5") (pin "1") (pinfunction "A_1") (pintype "passive"))
      (node (ref "DZ6") (pin "1") (pinfunction "A_1") (pintype "passive"))
      (node (ref "L6") (pin "1") (pinfunction "1_1") (pintype "passive"))
      (node (ref "M1") (pin "2") (pinfunction "GND_2") (pintype "passive"))
      (node (ref "MU1") (pin "2") (pinfunction "GND_2") (pintype "passive"))
      (node (ref "R1") (pin "2") (pinfunction "2_2") (pintype "passive"))
      (node (ref "R16") (pin "2") (pinfunction "2_2") (pintype "passive"))
      (node (ref "R17") (pin "2") (pinfunction "2_2") (pintype "passive"))
      (node (ref "R18") (pin "2") (pinfunction "2_2") (pintype "passive"))
      (node (ref "R19") (pin "2") (pinfunction "2_2") (pintype "passive"))
      (node (ref "R20") (pin "1") (pinfunction "1_1") (pintype "passive"))
      (node (ref "R26") (pin "2") (pinfunction "2_2") (pintype "passive"))
      (node (ref "R9") (pin "2") (pinfunction "2_2") (pintype "passive"))
      (node (ref "S1") (pin "1") (pinfunction "1_1") (pintype "passive"))
      (node (ref "S2") (pin "2") (pinfunction "2_2") (pintype "passive"))
      (node (ref "SC1") (pin "2") (pinfunction "-_2") (pintype "passive"))
      (node (ref "U1") (pin "1") (pinfunction "GND_1") (pintype "power_in"))
      (node (ref "U1") (pin "101") (pinfunction "GND_PAD_101") (pintype "power_in"))
      (node (ref "U2") (pin "1") (pinfunction "GND_1") (pintype "passive"))
      (node (ref "USB1") (pin "5") (pinfunction "GND_5") (pintype "passive"))
      (node (ref "USB2") (pin "5") (pinfunction "GND_5") (pintype "passive"))
    )
    (net (code "29") (name "GND IN") (class "Default")
      (node (ref "*3") (pin "2") (pinfunction "--_2") (pintype "passive"))
      (node (ref "*4") (pin "2") (pinfunction "--_2") (pintype "passive"))
      (node (ref "*5") (pin "2") (pinfunction "--_2") (pintype "passive"))
      (node (ref "C16") (pin "1") (pinfunction "1_1") (pintype "passive"))
      (node (ref "C17") (pin "1") (pinfunction "1_1") (pintype "passive"))
      (node (ref "C18") (pin "1") (pinfunction "1_1") (pintype "passive"))
      (node (ref "C19") (pin "2") (pinfunction "2_2") (pintype "passive"))
      (node (ref "J4") (pin "1") (pinfunction "1_1") (pintype "passive"))
      (node (ref "L6") (pin "2") (pinfunction "2_2") (pintype "passive"))
    )
    (net (code "30") (name "Net-(*2-Pad1)") (class "Default")
      (node (ref "*2") (pin "1") (pintype "passive"))
      (node (ref "*2") (pin "3") (pintype "passive"))
      (node (ref "D5") (pin "1") (pinfunction "1_1") (pintype "passive"))
      (node (ref "R5") (pin "2") (pinfunction "2_2") (pintype "passive"))
      (node (ref "R6") (pin "2") (pinfunction "2_2") (pintype "passive"))
    )
    (net (code "31") (name "Net-(*3-+)") (class "Default")
      (node (ref "*3") (pin "1") (pinfunction "+_1") (pintype "passive"))
      (node (ref "C16") (pin "2") (pinfunction "2_2") (pintype "passive"))
      (node (ref "L3") (pin "1") (pinfunction "1_1") (pintype "passive"))
    )
    (net (code "32") (name "Net-(*3-~-Pad3)") (class "Default")
      (node (ref "*3") (pin "3") (pinfunction "~_3") (pintype "passive"))
      (node (ref "J1") (pin "1") (pinfunction "1_1") (pintype "passive"))
    )
    (net (code "33") (name "Net-(*3-~-Pad4)") (class "Default")
      (node (ref "*3") (pin "4") (pinfunction "~_4") (pintype "passive"))
      (node (ref "J1") (pin "2") (pinfunction "2_2") (pintype "passive"))
    )
    (net (code "34") (name "Net-(*4-+)") (class "Default")
      (node (ref "*4") (pin "1") (pinfunction "+_1") (pintype "passive"))
      (node (ref "C17") (pin "2") (pinfunction "2_2") (pintype "passive"))
      (node (ref "L4") (pin "1") (pinfunction "1_1") (pintype "passive"))
    )
    (net (code "35") (name "Net-(*4-~-Pad3)") (class "Default")
      (node (ref "*4") (pin "3") (pinfunction "~_3") (pintype "passive"))
      (node (ref "J2") (pin "1") (pinfunction "1_1") (pintype "passive"))
    )
    (net (code "36") (name "Net-(*4-~-Pad4)") (class "Default")
      (node (ref "*4") (pin "4") (pinfunction "~_4") (pintype "passive"))
      (node (ref "J2") (pin "2") (pinfunction "2_2") (pintype "passive"))
    )
    (net (code "37") (name "Net-(*5-+)") (class "Default")
      (node (ref "*5") (pin "1") (pinfunction "+_1") (pintype "passive"))
      (node (ref "C18") (pin "2") (pinfunction "2_2") (pintype "passive"))
      (node (ref "L5") (pin "1") (pinfunction "1_1") (pintype "passive"))
    )
    (net (code "38") (name "Net-(*5-~-Pad3)") (class "Default")
      (node (ref "*5") (pin "3") (pinfunction "~_3") (pintype "passive"))
      (node (ref "J3") (pin "1") (pinfunction "1_1") (pintype "passive"))
    )
    (net (code "39") (name "Net-(*5-~-Pad4)") (class "Default")
      (node (ref "*5") (pin "4") (pinfunction "~_4") (pintype "passive"))
      (node (ref "J3") (pin "2") (pinfunction "2_2") (pintype "passive"))
    )
    (net (code "40") (name "Net-(B1-AAM)") (class "Default")
      (node (ref "B1") (pin "1") (pinfunction "AAM_1") (pintype "passive"))
      (node (ref "R1") (pin "1") (pinfunction "1_1") (pintype "passive"))
      (node (ref "R2") (pin "2") (pinfunction "2_2") (pintype "passive"))
    )
    (net (code "41") (name "Net-(B1-BST)") (class "Default")
      (node (ref "B1") (pin "5") (pinfunction "BST_5") (pintype "passive"))
      (node (ref "R3") (pin "2") (pinfunction "2_2") (pintype "passive"))
    )
    (net (code "42") (name "Net-(B1-EN{slash}SYNC)") (class "Default")
      (node (ref "B1") (pin "6") (pinfunction "EN/SYNC_6") (pintype "passive"))
      (node (ref "R4") (pin "2") (pinfunction "2_2") (pintype "passive"))
    )
    (net (code "43") (name "Net-(B1-FB)") (class "Default")
      (node (ref "B1") (pin "8") (pinfunction "FB_8") (pintype "passive"))
      (node (ref "R8") (pin "1") (pinfunction "1_1") (pintype "passive"))
    )
    (net (code "44") (name "Net-(B1-SW)") (class "Default")
      (node (ref "B1") (pin "3") (pinfunction "SW_3") (pintype "passive"))
      (node (ref "C2") (pin "1") (pinfunction "1_1") (pintype "passive"))
      (node (ref "L1") (pin "1") (pinfunction "1_1") (pintype "passive"))
    )
    (net (code "45") (name "Net-(B1-VCC)") (class "Default")
      (node (ref "B1") (pin "7") (pinfunction "VCC_7") (pintype "passive"))
      (node (ref "C1") (pin "1") (pinfunction "1_1") (pintype "passive"))
      (node (ref "R2") (pin "1") (pinfunction "1_1") (pintype "passive"))
    )
    (net (code "46") (name "Net-(C2-Pad2)") (class "Default")
      (node (ref "C2") (pin "2") (pinfunction "2_2") (pintype "passive"))
      (node (ref "R3") (pin "1") (pinfunction "1_1") (pintype "passive"))
    )
    (net (code "47") (name "Net-(C8-Pad1)") (class "Default")
      (node (ref "C8") (pin "1") (pinfunction "1_1") (pintype "passive"))
      (node (ref "R7") (pin "2") (pinfunction "2_2") (pintype "passive"))
      (node (ref "R8") (pin "2") (pinfunction "2_2") (pintype "passive"))
      (node (ref "R9") (pin "1") (pinfunction "1_1") (pintype "passive"))
    )
    (net (code "48") (name "Net-(C19-Pad1)") (class "Default")
      (node (ref "C19") (pin "1") (pinfunction "1_1") (pintype "passive"))
      (node (ref "D6") (pin "2") (pinfunction "2_2") (pintype "passive"))
      (node (ref "D7") (pin "2") (pinfunction "2_2") (pintype "passive"))
      (node (ref "D8") (pin "2") (pinfunction "2_2") (pintype "passive"))
      (node (ref "D9") (pin "2") (pinfunction "2_2") (pintype "passive"))
      (node (ref "L2") (pin "1") (pinfunction "1_1") (pintype "passive"))
    )
    (net (code "49") (name "Net-(D2-Pad2)") (class "Default")
      (node (ref "D2") (pin "2") (pinfunction "2_2") (pintype "passive"))
      (node (ref "D3") (pin "1") (pinfunction "1_1") (pintype "passive"))
      (node (ref "SB1") (pin "1") (pintype "passive"))
    )
    (net (code "50") (name "Net-(LED1-Pad1)") (class "Default")
      (node (ref "LED1") (pin "1") (pinfunction "1_1") (pintype "passive"))
      (node (ref "R21") (pin "1") (pinfunction "1_1") (pintype "passive"))
    )
    (net (code "51") (name "Net-(LED2-Pad2)") (class "Default")
      (node (ref "LED2") (pin "2") (pinfunction "2_2") (pintype "passive"))
      (node (ref "R26") (pin "1") (pinfunction "1_1") (pintype "passive"))
    )
    (net (code "52") (name "Net-(M1-ANT)") (class "Default")
      (node (ref "*6") (pin "1") (pinfunction "1_1") (pintype "passive"))
      (node (ref "M1") (pin "6") (pinfunction "ANT_6") (pintype "passive"))
    )
    (net (code "53") (name "Net-(M1-SET)") (class "Default")
      (node (ref "M1") (pin "5") (pinfunction "SET_5") (pintype "passive"))
      (node (ref "SB2") (pin "2") (pinfunction "2_2") (pintype "passive"))
    )
    (net (code "54") (name "Net-(Q1-B)") (class "Default")
      (node (ref "Q1") (pin "2") (pinfunction "B_2") (pintype "passive"))
      (node (ref "R23") (pin "1") (pinfunction "1_1") (pintype "passive"))
    )
    (net (code "55") (name "Net-(Q2-B)") (class "Default")
      (node (ref "Q2") (pin "2") (pinfunction "B_2") (pintype "passive"))
      (node (ref "R25") (pin "1") (pinfunction "1_1") (pintype "passive"))
    )
    (net (code "56") (name "Net-(SC1-+)") (class "Default")
      (node (ref "*1") (pin "1") (pintype "passive"))
      (node (ref "*1") (pin "3") (pintype "passive"))
      (node (ref "*2") (pin "2") (pintype "passive"))
      (node (ref "D4") (pin "1") (pinfunction "1_1") (pintype "passive"))
      (node (ref "D5") (pin "2") (pinfunction "2_2") (pintype "passive"))
      (node (ref "SC1") (pin "1") (pinfunction "+_1") (pintype "passive"))
    )
    (net (code "57") (name "Net-(U1-IO32{slash}ADC1:4{slash}TOUCH9{slash}XTAL-32K-P)") (class "Default")
      (node (ref "C23") (pin "1") (pinfunction "1_1") (pintype "passive"))
      (node (ref "U1") (pin "8") (pinfunction "IO32/ADC1:4/TOUCH9/XTAL-32K-P_8") (pintype "passive"))
      (node (ref "X1") (pin "2") (pinfunction "2_2") (pintype "passive"))
    )
    (net (code "58") (name "Net-(U1-IO33{slash}ADC1:5{slash}TOUCH8{slash}XTAL-32K-N)") (class "Default")
      (node (ref "C25") (pin "1") (pinfunction "1_1") (pintype "passive"))
      (node (ref "U1") (pin "9") (pinfunction "IO33/ADC1:5/TOUCH8/XTAL-32K-N_9") (pintype "passive"))
      (node (ref "X1") (pin "1") (pinfunction "1_1") (pintype "passive"))
    )
    (net (code "59") (name "Net-(U2-D+)") (class "Default")
      (node (ref "U2") (pin "5") (pinfunction "D+_5") (pintype "passive"))
      (node (ref "USB2") (pin "3") (pinfunction "D+/DM_3") (pintype "passive"))
    )
    (net (code "60") (name "Net-(U2-D-)") (class "Default")
      (node (ref "U2") (pin "6") (pinfunction "D-_6") (pintype "passive"))
      (node (ref "USB2") (pin "2") (pinfunction "D-/DM_2") (pintype "passive"))
    )
    (net (code "61") (name "Net-(U2-XI)") (class "Default")
      (node (ref "C24") (pin "1") (pinfunction "1_1") (pintype "passive"))
      (node (ref "U2") (pin "7") (pinfunction "XI_7") (pintype "passive"))
      (node (ref "X2") (pin "2") (pinfunction "2_2") (pintype "passive"))
    )
    (net (code "62") (name "Net-(U2-XO)") (class "Default")
      (node (ref "C26") (pin "1") (pinfunction "1_1") (pintype "passive"))
      (node (ref "U2") (pin "8") (pinfunction "XO_8") (pintype "passive"))
      (node (ref "X2") (pin "1") (pinfunction "1_1") (pintype "passive"))
    )
    (net (code "63") (name "Net-(USB1-VCC)") (class "Default")
      (node (ref "D10") (pin "1") (pinfunction "1_1") (pintype "passive"))
      (node (ref "USB1") (pin "1") (pinfunction "VCC_1") (pintype "passive"))
    )
    (net (code "64") (name "Net-(USB2-VCC)") (class "Default")
      (node (ref "D11") (pin "1") (pinfunction "1_1") (pintype "passive"))
      (node (ref "USB2") (pin "1") (pinfunction "VCC_1") (pintype "passive"))
    )
    (net (code "65") (name "VCC IN") (class "Default")
      (node (ref "D7") (pin "1") (pinfunction "1_1") (pintype "passive"))
      (node (ref "J4") (pin "2") (pinfunction "2_2") (pintype "passive"))
    )
    (net (code "66") (name "V_BUCK") (class "Default")
      (node (ref "*TP1") (pin "1") (pintype "passive"))
      (node (ref "B1") (pin "2") (pinfunction "IN_2") (pintype "passive"))
      (node (ref "C3") (pin "1") (pinfunction "1_1") (pintype "passive"))
      (node (ref "D1") (pin "2") (pinfunction "2_2") (pintype "passive"))
      (node (ref "L2") (pin "2") (pinfunction "2_2") (pintype "passive"))
      (node (ref "R13") (pin "1") (pinfunction "1_1") (pintype "passive"))
      (node (ref "R4") (pin "1") (pinfunction "1_1") (pintype "passive"))
    )
    (net (code "67") (name "unconnected-(MU1-AD0-Pad7)") (class "Default")
      (node (ref "MU1") (pin "7") (pinfunction "AD0_7") (pintype "passive"))
    )
    (net (code "68") (name "unconnected-(MU1-INT-Pad8)") (class "Default")
      (node (ref "MU1") (pin "8") (pinfunction "INT_8") (pintype "passive"))
    )
    (net (code "69") (name "unconnected-(MU1-XCL-Pad6)") (class "Default")
      (node (ref "MU1") (pin "6") (pinfunction "XCL_6") (pintype "passive"))
    )
    (net (code "70") (name "unconnected-(MU1-XDA-Pad5)") (class "Default")
      (node (ref "MU1") (pin "5") (pinfunction "XDA_5") (pintype "passive"))
    )
    (net (code "71") (name "unconnected-(U1-CLK-Pad20)") (class "Default")
      (node (ref "U1") (pin "20") (pinfunction "CLK_20") (pintype "passive"))
    )
    (net (code "72") (name "unconnected-(U1-CMD-Pad19)") (class "Default")
      (node (ref "U1") (pin "19") (pinfunction "CMD_19") (pintype "passive"))
    )
    (net (code "73") (name "unconnected-(U1-GND-Pad15)") (class "Default")
      (node (ref "U1") (pin "15") (pinfunction "GND_15") (pintype "power_in"))
    )
    (net (code "74") (name "unconnected-(U1-GND-Pad38)") (class "Default")
      (node (ref "U1") (pin "38") (pinfunction "GND_38") (pintype "power_in"))
    )
    (net (code "75") (name "unconnected-(U1-IO4{slash}ADC2:0{slash}TOUCH0{slash}HSPIHD-Pad26)") (class "Default")
      (node (ref "U1") (pin "26") (pinfunction "IO4/ADC2:0/TOUCH0/HSPIHD_26") (pintype "passive"))
    )
    (net (code "76") (name "unconnected-(U1-IO18{slash}VSPICLK{slash}HS1-DATA7-Pad30)") (class "Default")
      (node (ref "U1") (pin "30") (pinfunction "IO18/VSPICLK/HS1-DATA7_30") (pintype "passive"))
    )
    (net (code "77") (name "unconnected-(U1-IO19{slash}VSPIQ{slash}HS-DATA2-Pad31)") (class "Default")
      (node (ref "U1") (pin "31") (pinfunction "IO19/VSPIQ/HS-DATA2_31") (pintype "passive"))
    )
    (net (code "78") (name "unconnected-(U1-IO23-Pad37)") (class "Default")
      (node (ref "U1") (pin "37") (pinfunction "IO23_37") (pintype "passive"))
    )
    (net (code "79") (name "unconnected-(U1-IO25{slash}ADC2:8{slash}DAC1-Pad10)") (class "Default")
      (node (ref "U1") (pin "10") (pinfunction "IO25/ADC2:8/DAC1_10") (pintype "passive"))
    )
    (net (code "80") (name "unconnected-(U1-IO26{slash}ADC2:9{slash}DAC2-Pad11)") (class "Default")
      (node (ref "U1") (pin "11") (pinfunction "IO26/ADC2:9/DAC2_11") (pintype "passive"))
    )
    (net (code "81") (name "unconnected-(U1-NC-Pad32)") (class "Default")
      (node (ref "U1") (pin "32") (pinfunction "NC_32") (pintype "passive"))
    )
    (net (code "82") (name "unconnected-(U1-SD0-Pad21)") (class "Default")
      (node (ref "U1") (pin "21") (pinfunction "SD0_21") (pintype "passive"))
    )
    (net (code "83") (name "unconnected-(U1-SD1-Pad22)") (class "Default")
      (node (ref "U1") (pin "22") (pinfunction "SD1_22") (pintype "passive"))
    )
    (net (code "84") (name "unconnected-(U1-SD2-Pad17)") (class "Default")
      (node (ref "U1") (pin "17") (pinfunction "SD2_17") (pintype "passive"))
    )
    (net (code "85") (name "unconnected-(U1-SD3-Pad18)") (class "Default")
      (node (ref "U1") (pin "18") (pinfunction "SD3_18") (pintype "passive"))
    )
    (net (code "86") (name "unconnected-(U2-3V-Pad4)") (class "Default")
      (node (ref "U2") (pin "4") (pinfunction "3V_4") (pintype "passive"))
    )
    (net (code "87") (name "unconnected-(U2-CTR#-Pad9)") (class "Default")
      (node (ref "U2") (pin "9") (pinfunction "CTR#_9") (pintype "passive"))
    )
    (net (code "88") (name "unconnected-(U2-DCD#-Pad12)") (class "Default")
      (node (ref "U2") (pin "12") (pinfunction "DCD#_12") (pintype "passive"))
    )
    (net (code "89") (name "unconnected-(U2-DSR#-Pad10)") (class "Default")
      (node (ref "U2") (pin "10") (pinfunction "DSR#_10") (pintype "passive"))
    )
    (net (code "90") (name "unconnected-(U2-RI#-Pad11)") (class "Default")
      (node (ref "U2") (pin "11") (pinfunction "RI#_11") (pintype "passive"))
    )
    (net (code "91") (name "unconnected-(U2-RS232-Pad15)") (class "Default")
      (node (ref "U2") (pin "15") (pinfunction "RS232_15") (pintype "passive"))
    )
    (net (code "92") (name "unconnected-(USB2-ID-Pad4)") (class "Default")
      (node (ref "USB2") (pin "4") (pinfunction "ID_4") (pintype "passive"))
    )
  )
)
